# PowerSupplyCarlos.net
KiCad netlist of a schematic drawn in EAGLE
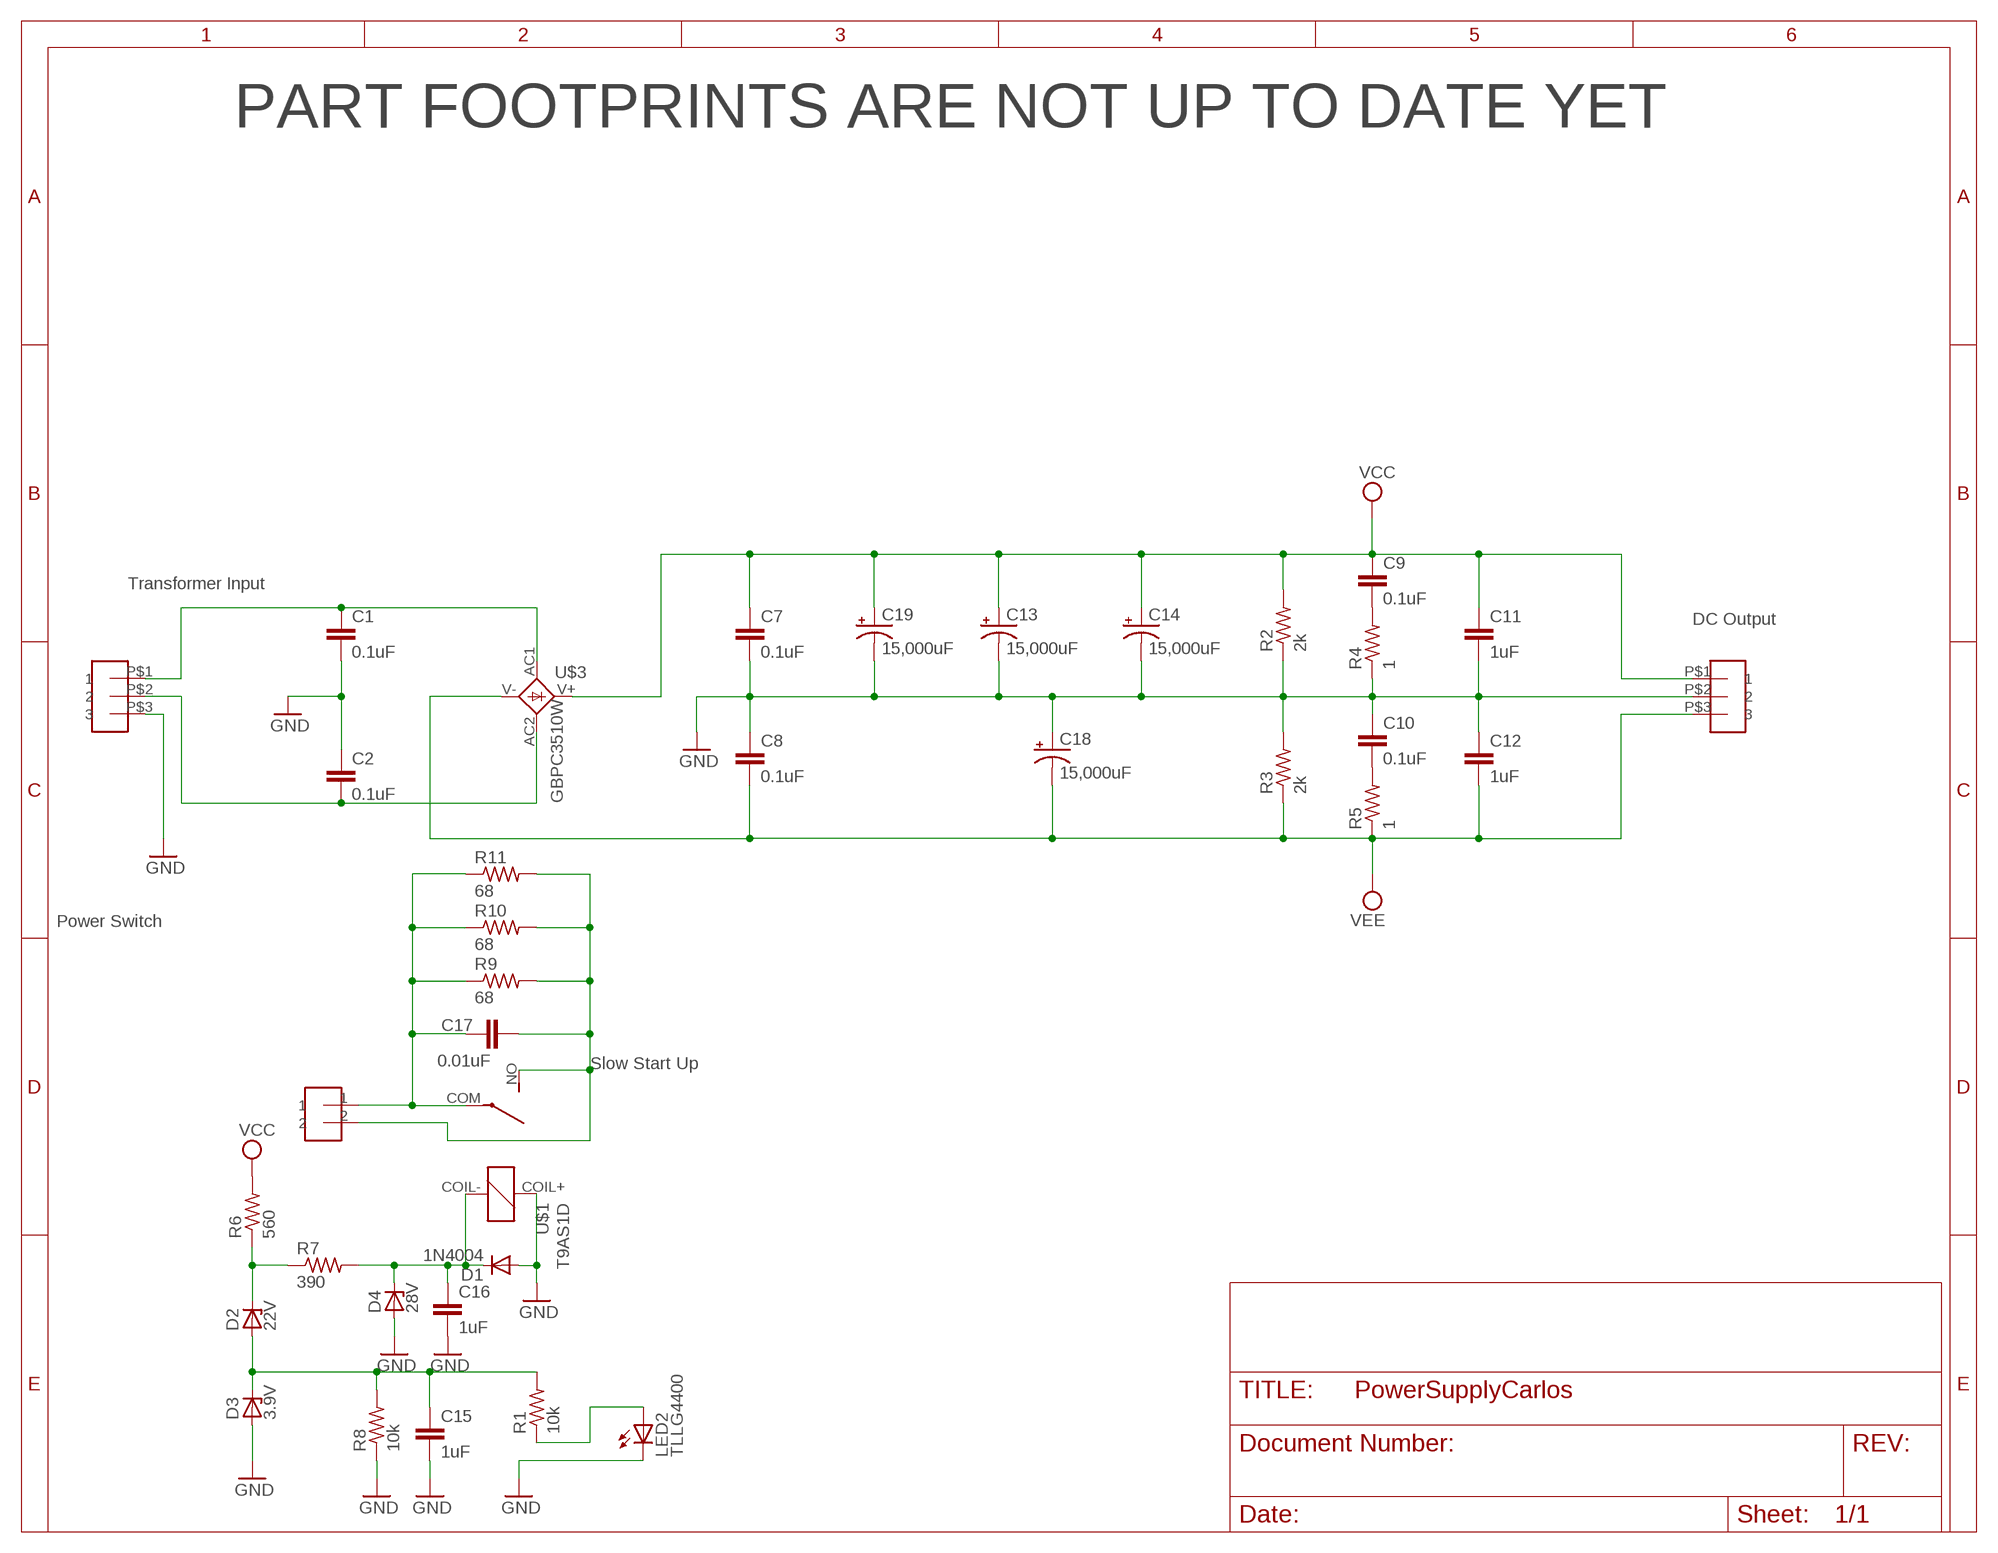
[diagram p0: schematic, sheet 1]

(export (version "E")
  (design (tool "Eeschema 10.0.6"))
  (components
    (comp (ref "C1")
      (value "0.1uF")
      (footprint "eagle-import:C102-064X133")
      (libsource (lib "eagle-import") (part "C-EU102-064X133"))
    )
    (comp (ref "C2")
      (value "0.1uF")
      (footprint "eagle-import:C102-064X133")
      (libsource (lib "eagle-import") (part "C-EU102-064X133"))
    )
    (comp (ref "C7")
      (value "0.1uF")
      (footprint "eagle-import:C102-064X133")
      (libsource (lib "eagle-import") (part "C-EU102-064X133"))
    )
    (comp (ref "C8")
      (value "0.1uF")
      (footprint "eagle-import:C102-064X133")
      (libsource (lib "eagle-import") (part "C-EU102-064X133"))
    )
    (comp (ref "C9")
      (value "0.1uF")
      (footprint "eagle-import:C102-064X133")
      (libsource (lib "eagle-import") (part "C-EU102-064X133"))
    )
    (comp (ref "C10")
      (value "0.1uF")
      (footprint "eagle-import:C102-064X133")
      (libsource (lib "eagle-import") (part "C-EU102-064X133"))
    )
    (comp (ref "C11")
      (value "1uF")
      (footprint "eagle-import:C102-064X133")
      (libsource (lib "eagle-import") (part "C-EU102-064X133"))
    )
    (comp (ref "C12")
      (value "1uF")
      (footprint "eagle-import:C102-064X133")
      (libsource (lib "eagle-import") (part "C-EU102-064X133"))
    )
    (comp (ref "C13")
      (value "15,000uF")
      (footprint "eagle-import:PHI-35")
      (libsource (lib "eagle-import") (part "LNR1K153MSE"))
    )
    (comp (ref "C14")
      (value "15,000uF")
      (footprint "eagle-import:PHI-35")
      (libsource (lib "eagle-import") (part "LNR1K153MSE"))
    )
    (comp (ref "C15")
      (value "1uF")
      (footprint "eagle-import:C025-060X050")
      (libsource (lib "eagle-import") (part "C-EU025-060X050"))
    )
    (comp (ref "C16")
      (value "1uF")
      (footprint "eagle-import:C025-060X050")
      (libsource (lib "eagle-import") (part "C-EU025-060X050"))
    )
    (comp (ref "C17")
      (value "0.01uF")
      (footprint "eagle-import:C025-060X050")
      (libsource (lib "eagle-import") (part "C-EU025-060X050"))
    )
    (comp (ref "C18")
      (value "15,000uF")
      (footprint "eagle-import:PHI-45")
      (libsource (lib "eagle-import") (part "36X10222"))
    )
    (comp (ref "C19")
      (value "15,000uF")
      (footprint "eagle-import:PHI-35")
      (libsource (lib "eagle-import") (part "LNR1K153MSE"))
    )
    (comp (ref "D1")
      (value "1N4004")
      (footprint "eagle-import:DO41-10")
      (libsource (lib "eagle-import") (part "1N4004"))
    )
    (comp (ref "D2")
      (value "22V")
      (footprint "eagle-import:P1Z12")
      (libsource (lib "eagle-import") (part "ZENER-DIODEP1-12"))
    )
    (comp (ref "D3")
      (value "3.9V")
      (footprint "eagle-import:DO34Z7")
      (libsource (lib "eagle-import") (part "ZENER-DIODEDO34-7"))
    )
    (comp (ref "D4")
      (value "28V")
      (footprint "eagle-import:P1Z12")
      (libsource (lib "eagle-import") (part "ZENER-DIODEP1-12"))
    )
    (comp (ref "LED2")
      (value "TLLG4400")
      (footprint "eagle-import:LED3MM")
      (fields (field (name "MF") "VISHAY SEMICONDUCTOR"))
      (libsource (lib "eagle-import") (part "TLLG4400"))
    )
    (comp (ref "P1")
      (value "3PIN_3.25MM")
      (footprint "eagle-import:3PIN_SCREW_EYELET")
      (libsource (lib "eagle-import") (part "3PIN_3.25MM"))
    )
    (comp (ref "P2")
      (value "3PIN_3.25MM")
      (footprint "eagle-import:3PIN_SCREW_EYELET")
      (libsource (lib "eagle-import") (part "3PIN_3.25MM"))
    )
    (comp (ref "R1")
      (value "10k")
      (footprint "eagle-import:0207_15")
      (libsource (lib "eagle-import") (part "resistor_R-US_0207/15"))
    )
    (comp (ref "R2")
      (value "2k")
      (footprint "eagle-import:VTA52")
      (libsource (lib "eagle-import") (part "R-US_VTA52"))
    )
    (comp (ref "R3")
      (value "2k")
      (footprint "eagle-import:VTA52")
      (libsource (lib "eagle-import") (part "R-US_VTA52"))
    )
    (comp (ref "R4")
      (value "1")
      (footprint "eagle-import:0411_12")
      (libsource (lib "eagle-import") (part "R-US_0411/12"))
    )
    (comp (ref "R5")
      (value "1")
      (footprint "eagle-import:0411_12")
      (libsource (lib "eagle-import") (part "R-US_0411/12"))
    )
    (comp (ref "R6")
      (value "560")
      (footprint "eagle-import:0207_15")
      (libsource (lib "eagle-import") (part "resistor_R-US_0207/15"))
    )
    (comp (ref "R7")
      (value "390")
      (footprint "eagle-import:0207_15")
      (libsource (lib "eagle-import") (part "resistor_R-US_0207/15"))
    )
    (comp (ref "R8")
      (value "10k")
      (footprint "eagle-import:0207_15")
      (libsource (lib "eagle-import") (part "resistor_R-US_0207/15"))
    )
    (comp (ref "R9")
      (value "68")
      (footprint "eagle-import:0617_22")
      (libsource (lib "eagle-import") (part "R-US_0617/22"))
    )
    (comp (ref "R10")
      (value "68")
      (footprint "eagle-import:0617_22")
      (libsource (lib "eagle-import") (part "R-US_0617/22"))
    )
    (comp (ref "R11")
      (value "68")
      (footprint "eagle-import:0617_22")
      (libsource (lib "eagle-import") (part "R-US_0617/22"))
    )
    (comp (ref "U$1")
      (value "T9AS1D")
      (footprint "eagle-import:RELAY_CM")
      (libsource (lib "eagle-import") (part "T9AS1D"))
    )
    (comp (ref "U$3")
      (value "GBPC3510W")
      (footprint "eagle-import:GBPC3510W")
      (libsource (lib "eagle-import") (part "GBPC3510W"))
    )
    (comp (ref "U$4")
      (value "1X2HEADER_100MIL")
      (footprint "eagle-import:1X2_100MIL")
      (libsource (lib "eagle-import") (part "1X2HEADER_100MIL"))
    )
  )
  (nets
    (net (code "1") (name "GND") (class "Default")
      (node (ref "C1") (pin "2") (pinfunction "2_2") (pintype "passive"))
      (node (ref "C10") (pin "1") (pinfunction "1_1") (pintype "passive"))
      (node (ref "C11") (pin "2") (pinfunction "2_2") (pintype "passive"))
      (node (ref "C12") (pin "1") (pinfunction "1_1") (pintype "passive"))
      (node (ref "C13") (pin "-") (pinfunction "-_-") (pintype "passive"))
      (node (ref "C14") (pin "-") (pinfunction "-_-") (pintype "passive"))
      (node (ref "C15") (pin "2") (pinfunction "2_2") (pintype "passive"))
      (node (ref "C16") (pin "2") (pinfunction "2_2") (pintype "passive"))
      (node (ref "C18") (pin "+") (pinfunction "+_+") (pintype "passive"))
      (node (ref "C19") (pin "-") (pinfunction "-_-") (pintype "passive"))
      (node (ref "C2") (pin "1") (pinfunction "1_1") (pintype "passive"))
      (node (ref "C7") (pin "2") (pinfunction "2_2") (pintype "passive"))
      (node (ref "C8") (pin "1") (pinfunction "1_1") (pintype "passive"))
      (node (ref "D1") (pin "A") (pinfunction "A_A") (pintype "passive"))
      (node (ref "D3") (pin "A") (pinfunction "A_A") (pintype "passive"))
      (node (ref "D4") (pin "A") (pinfunction "A_A") (pintype "passive"))
      (node (ref "LED2") (pin "K") (pinfunction "C_K") (pintype "passive"))
      (node (ref "P1") (pin "P$3") (pinfunction "3_P$3") (pintype "bidirectional"))
      (node (ref "P2") (pin "P$2") (pinfunction "2_P$2") (pintype "bidirectional"))
      (node (ref "R2") (pin "1") (pinfunction "1_1") (pintype "passive"))
      (node (ref "R3") (pin "2") (pinfunction "2_2") (pintype "passive"))
      (node (ref "R4") (pin "1") (pinfunction "1_1") (pintype "passive"))
      (node (ref "R8") (pin "1") (pinfunction "1_1") (pintype "passive"))
      (node (ref "U$1") (pin "COIL+") (pinfunction "COIL+_COIL+") (pintype "passive"))
    )
    (net (code "2") (name "Net-(C9-Pad2)") (class "Default")
      (node (ref "C9") (pin "2") (pinfunction "2_2") (pintype "passive"))
      (node (ref "R4") (pin "2") (pinfunction "2_2") (pintype "passive"))
    )
    (net (code "3") (name "Net-(C10-Pad2)") (class "Default")
      (node (ref "C10") (pin "2") (pinfunction "2_2") (pintype "passive"))
      (node (ref "R5") (pin "2") (pinfunction "2_2") (pintype "passive"))
    )
    (net (code "4") (name "Net-(C15-Pad1)") (class "Default")
      (node (ref "C15") (pin "1") (pinfunction "1_1") (pintype "passive"))
      (node (ref "D2") (pin "A") (pinfunction "A_A") (pintype "passive"))
      (node (ref "D3") (pin "C") (pinfunction "C_C") (pintype "passive"))
      (node (ref "R1") (pin "2") (pinfunction "2_2") (pintype "passive"))
      (node (ref "R8") (pin "2") (pinfunction "2_2") (pintype "passive"))
    )
    (net (code "5") (name "Net-(C16-Pad1)") (class "Default")
      (node (ref "C16") (pin "1") (pinfunction "1_1") (pintype "passive"))
      (node (ref "D1") (pin "C") (pinfunction "C_C") (pintype "passive"))
      (node (ref "D4") (pin "C") (pinfunction "C_C") (pintype "passive"))
      (node (ref "R7") (pin "2") (pinfunction "2_2") (pintype "passive"))
      (node (ref "U$1") (pin "COIL-") (pinfunction "COIL-_COIL-") (pintype "passive"))
    )
    (net (code "6") (name "Net-(C17-Pad1)") (class "Default")
      (node (ref "C17") (pin "1") (pinfunction "1_1") (pintype "passive"))
      (node (ref "R10") (pin "1") (pinfunction "1_1") (pintype "passive"))
      (node (ref "R11") (pin "1") (pinfunction "1_1") (pintype "passive"))
      (node (ref "R9") (pin "1") (pinfunction "1_1") (pintype "passive"))
      (node (ref "U$1") (pin "COM") (pinfunction "COM_COM") (pintype "passive"))
      (node (ref "U$4") (pin "1") (pinfunction "1_1") (pintype "bidirectional"))
    )
    (net (code "7") (name "Net-(C17-Pad2)") (class "Default")
      (node (ref "C17") (pin "2") (pinfunction "2_2") (pintype "passive"))
      (node (ref "R10") (pin "2") (pinfunction "2_2") (pintype "passive"))
      (node (ref "R11") (pin "2") (pinfunction "2_2") (pintype "passive"))
      (node (ref "R9") (pin "2") (pinfunction "2_2") (pintype "passive"))
      (node (ref "U$1") (pin "NO") (pinfunction "NO_NO") (pintype "passive"))
      (node (ref "U$4") (pin "2") (pinfunction "2_2") (pintype "bidirectional"))
    )
    (net (code "8") (name "Net-(D2-PadC)") (class "Default")
      (node (ref "D2") (pin "C") (pinfunction "C_C") (pintype "passive"))
      (node (ref "R6") (pin "1") (pinfunction "1_1") (pintype "passive"))
      (node (ref "R7") (pin "1") (pinfunction "1_1") (pintype "passive"))
    )
    (net (code "9") (name "Net-(LED2-PadA)") (class "Default")
      (node (ref "LED2") (pin "A") (pinfunction "A_A") (pintype "passive"))
      (node (ref "R1") (pin "1") (pinfunction "1_1") (pintype "passive"))
    )
    (net (code "10") (name "Net-(P1-1)") (class "Default")
      (node (ref "C1") (pin "1") (pinfunction "1_1") (pintype "passive"))
      (node (ref "P1") (pin "P$1") (pinfunction "1_P$1") (pintype "bidirectional"))
      (node (ref "U$3") (pin "AC1") (pinfunction "AC1_AC1") (pintype "passive"))
    )
    (net (code "11") (name "Net-(P1-2)") (class "Default")
      (node (ref "C2") (pin "2") (pinfunction "2_2") (pintype "passive"))
      (node (ref "P1") (pin "P$2") (pinfunction "2_P$2") (pintype "bidirectional"))
      (node (ref "U$3") (pin "AC2") (pinfunction "AC2_AC2") (pintype "passive"))
    )
    (net (code "12") (name "VCC") (class "Default")
      (node (ref "C11") (pin "1") (pinfunction "1_1") (pintype "passive"))
      (node (ref "C13") (pin "+") (pinfunction "+_+") (pintype "passive"))
      (node (ref "C14") (pin "+") (pinfunction "+_+") (pintype "passive"))
      (node (ref "C19") (pin "+") (pinfunction "+_+") (pintype "passive"))
      (node (ref "C7") (pin "1") (pinfunction "1_1") (pintype "passive"))
      (node (ref "C9") (pin "1") (pinfunction "1_1") (pintype "passive"))
      (node (ref "P2") (pin "P$1") (pinfunction "1_P$1") (pintype "bidirectional"))
      (node (ref "R2") (pin "2") (pinfunction "2_2") (pintype "passive"))
      (node (ref "R6") (pin "2") (pinfunction "2_2") (pintype "passive"))
      (node (ref "U$3") (pin "V+") (pinfunction "+_V+") (pintype "passive"))
    )
    (net (code "13") (name "VEE") (class "Default")
      (node (ref "C12") (pin "2") (pinfunction "2_2") (pintype "passive"))
      (node (ref "C18") (pin "+1") (pinfunction "-_+1") (pintype "passive"))
      (node (ref "C8") (pin "2") (pinfunction "2_2") (pintype "passive"))
      (node (ref "P2") (pin "P$3") (pinfunction "3_P$3") (pintype "bidirectional"))
      (node (ref "R3") (pin "1") (pinfunction "1_1") (pintype "passive"))
      (node (ref "R5") (pin "1") (pinfunction "1_1") (pintype "passive"))
      (node (ref "U$3") (pin "V-") (pinfunction "-_V-") (pintype "passive"))
    )
  )
)
